# Zio_9DOF_IMU_LSM9DS1.net
KiCad netlist of a schematic drawn in EAGLE
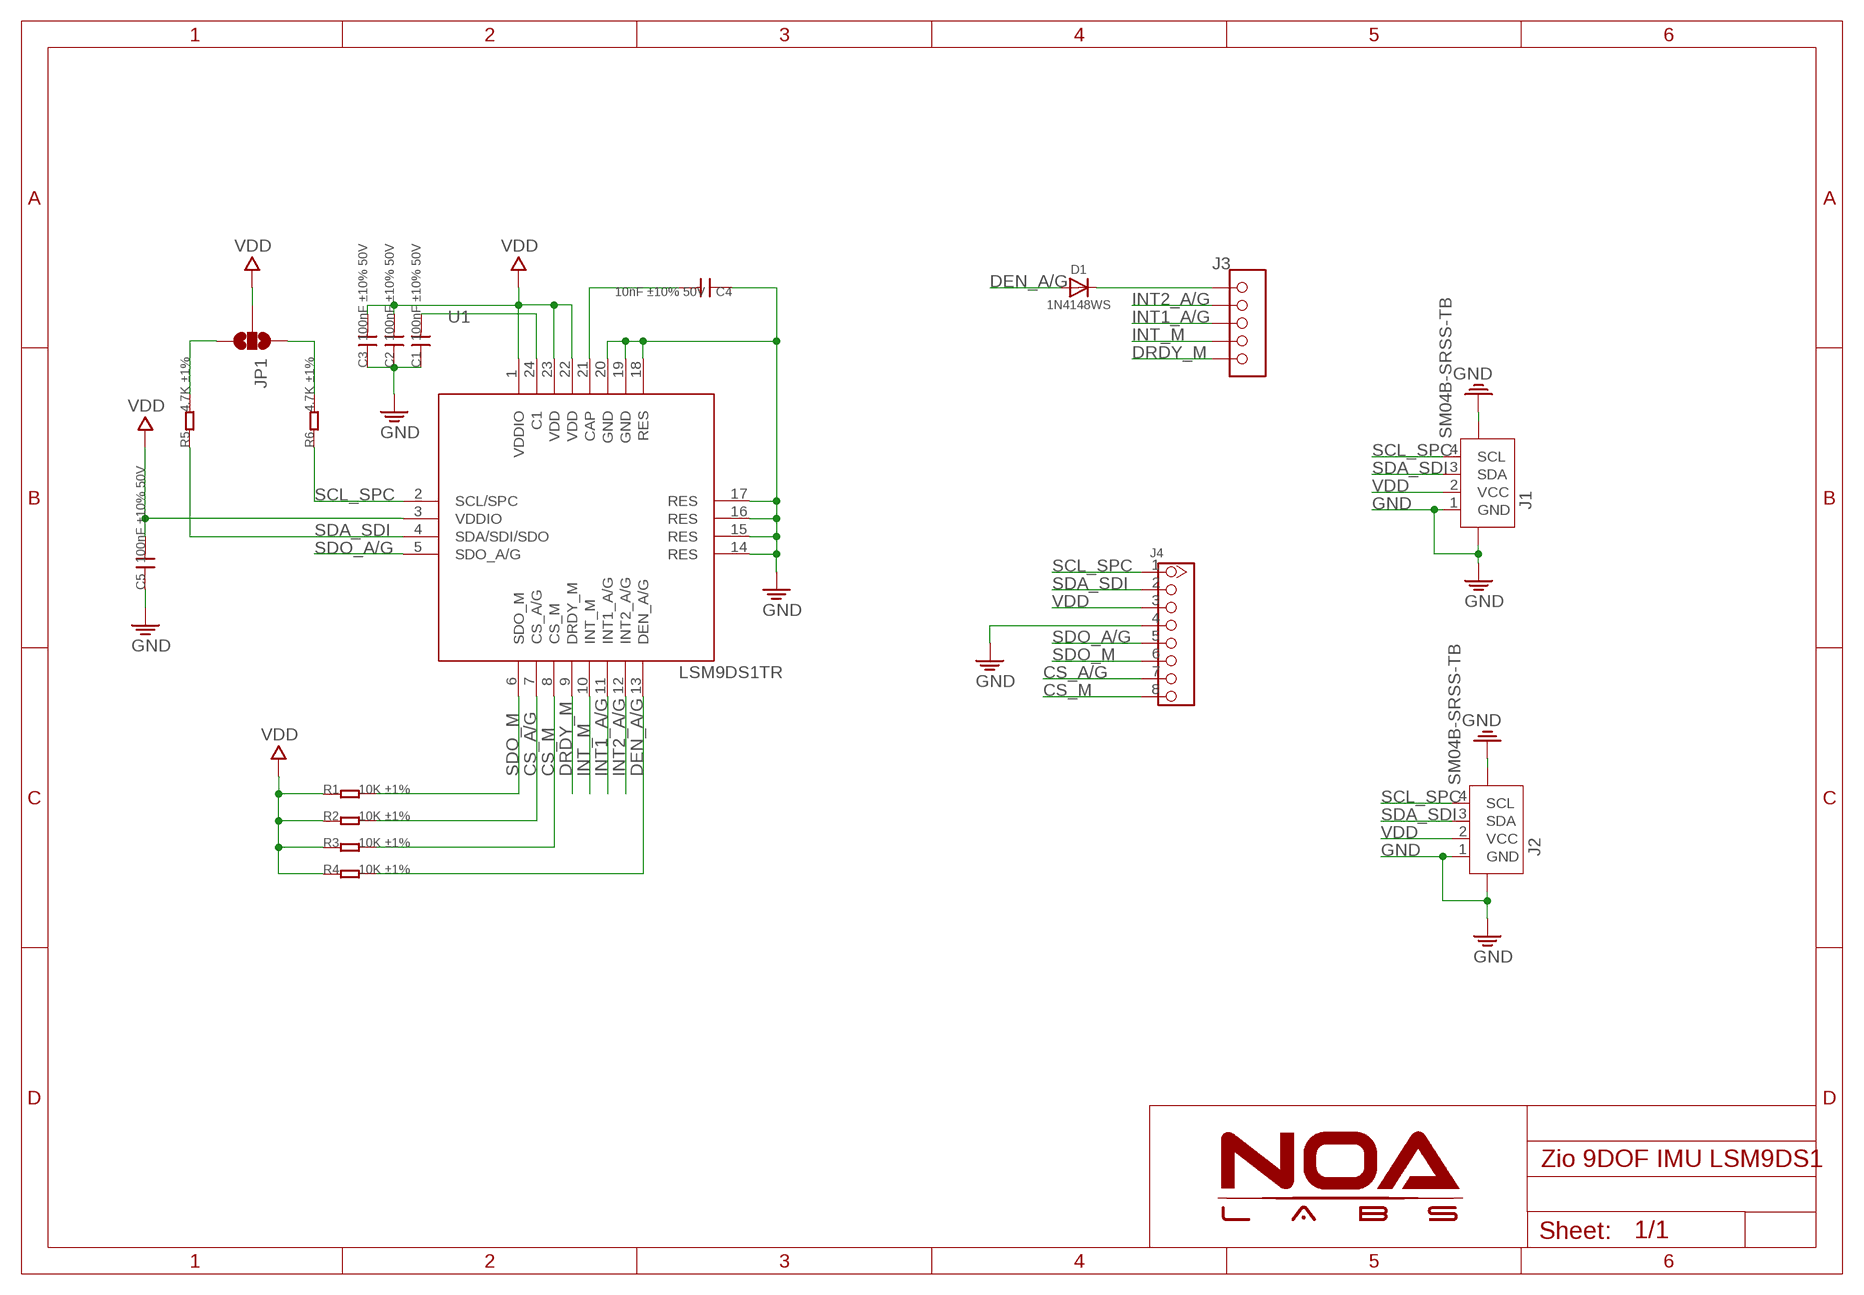
[diagram p0: schematic, sheet 1]

(export (version "E")
  (design (tool "Eeschema 10.0.6"))
  (components
    (comp (ref "C1")
      (value "100nF ±10% 50V")
      (footprint "eagle-import:0402")
      (libsource (lib "eagle-import") (part "C-0402"))
    )
    (comp (ref "C2")
      (value "100nF ±10% 50V")
      (footprint "eagle-import:0402")
      (libsource (lib "eagle-import") (part "C-0402"))
    )
    (comp (ref "C3")
      (value "100nF ±10% 50V")
      (footprint "eagle-import:0402")
      (libsource (lib "eagle-import") (part "C-0402"))
    )
    (comp (ref "C4")
      (value "10nF ±10% 50V")
      (footprint "eagle-import:0402")
      (libsource (lib "eagle-import") (part "C-0402"))
    )
    (comp (ref "C5")
      (value "100nF ±10% 50V")
      (footprint "eagle-import:0402")
      (libsource (lib "eagle-import") (part "C-0402"))
    )
    (comp (ref "D1")
      (value "1N4148WS")
      (footprint "eagle-import:SOD-323")
      (libsource (lib "eagle-import") (part "DIODESOD-323"))
    )
    (comp (ref "J1")
      (value "SM04B-SRSS-TB")
      (footprint "eagle-import:JST-SH-4P")
      (libsource (lib "eagle-import") (part "JST-SH-4P-1.0"))
    )
    (comp (ref "J2")
      (value "SM04B-SRSS-TB")
      (footprint "eagle-import:JST-SH-4P")
      (libsource (lib "eagle-import") (part "JST-SH-4P-1.0"))
    )
    (comp (ref "J3")
      (value "HEADER-5P-2.54")
      (footprint "eagle-import:5P-2.54")
      (libsource (lib "eagle-import") (part "HEADER-5P-2.54"))
    )
    (comp (ref "J4")
      (value "HEADER-8P-2.54")
      (footprint "eagle-import:8P-2.54")
      (libsource (lib "eagle-import") (part "HEADER-8P-2.54"))
    )
    (comp (ref "JP1")
      (value "JUMPER-SMT_3_2-NC_PASTE_NOCREM")
      (footprint "eagle-import:SMT-JUMPER_3_2-NC_PASTE_SILK_NOCREM")
      (libsource (lib "eagle-import") (part "JUMPER-SMT_3_2-NC_PASTE_NOCREM"))
    )
    (comp (ref "R1")
      (value "10K ±1%")
      (footprint "eagle-import:0402")
      (libsource (lib "eagle-import") (part "R-0402"))
    )
    (comp (ref "R2")
      (value "10K ±1%")
      (footprint "eagle-import:0402")
      (libsource (lib "eagle-import") (part "R-0402"))
    )
    (comp (ref "R3")
      (value "10K ±1%")
      (footprint "eagle-import:0402")
      (libsource (lib "eagle-import") (part "R-0402"))
    )
    (comp (ref "R4")
      (value "10K ±1%")
      (footprint "eagle-import:0402")
      (libsource (lib "eagle-import") (part "R-0402"))
    )
    (comp (ref "R5")
      (value "4.7K ±1%")
      (footprint "eagle-import:0402")
      (libsource (lib "eagle-import") (part "R-0402"))
    )
    (comp (ref "R6")
      (value "4.7K ±1%")
      (footprint "eagle-import:0402")
      (libsource (lib "eagle-import") (part "R-0402"))
    )
    (comp (ref "U1")
      (value "LSM9DS1TR")
      (footprint "eagle-import:LGA24")
      (libsource (lib "eagle-import") (part "LSM9DS1"))
    )
  )
  (nets
    (net (code "1") (name "/CS_A{slash}G") (class "Default")
      (node (ref "J4") (pin "7") (pinfunction "7_7") (pintype "bidirectional"))
      (node (ref "R2") (pin "2") (pinfunction "2_2") (pintype "passive"))
      (node (ref "U1") (pin "7") (pinfunction "CS_A/G_7") (pintype "bidirectional"))
    )
    (net (code "2") (name "/CS_M") (class "Default")
      (node (ref "J4") (pin "8") (pinfunction "8_8") (pintype "bidirectional"))
      (node (ref "R3") (pin "2") (pinfunction "2_2") (pintype "passive"))
      (node (ref "U1") (pin "8") (pinfunction "CS_M_8") (pintype "bidirectional"))
    )
    (net (code "3") (name "/DEN_A{slash}G") (class "Default")
      (node (ref "D1") (pin "A") (pinfunction "A_A") (pintype "passive"))
      (node (ref "R4") (pin "2") (pinfunction "2_2") (pintype "passive"))
      (node (ref "U1") (pin "13") (pinfunction "DEN_A/G_13") (pintype "bidirectional"))
    )
    (net (code "4") (name "/DRDY_M") (class "Default")
      (node (ref "J3") (pin "5") (pinfunction "5_5") (pintype "bidirectional"))
      (node (ref "U1") (pin "9") (pinfunction "DRDY_M_9") (pintype "bidirectional"))
    )
    (net (code "5") (name "/INT1_A{slash}G") (class "Default")
      (node (ref "J3") (pin "3") (pinfunction "3_3") (pintype "bidirectional"))
      (node (ref "U1") (pin "11") (pinfunction "INT1_A/G_11") (pintype "bidirectional"))
    )
    (net (code "6") (name "/INT2_A{slash}G") (class "Default")
      (node (ref "J3") (pin "2") (pinfunction "2_2") (pintype "bidirectional"))
      (node (ref "U1") (pin "12") (pinfunction "INT2_A/G_12") (pintype "bidirectional"))
    )
    (net (code "7") (name "/INT_M") (class "Default")
      (node (ref "J3") (pin "4") (pinfunction "4_4") (pintype "bidirectional"))
      (node (ref "U1") (pin "10") (pinfunction "INT_M_10") (pintype "bidirectional"))
    )
    (net (code "8") (name "/SCL_SPC") (class "Default")
      (node (ref "J1") (pin "4") (pinfunction "SCL_4") (pintype "bidirectional"))
      (node (ref "J2") (pin "4") (pinfunction "SCL_4") (pintype "bidirectional"))
      (node (ref "J4") (pin "1") (pinfunction "1_1") (pintype "bidirectional"))
      (node (ref "R6") (pin "1") (pinfunction "1_1") (pintype "passive"))
      (node (ref "U1") (pin "2") (pinfunction "SCL/SPC_2") (pintype "bidirectional"))
    )
    (net (code "9") (name "/SDA_SDI") (class "Default")
      (node (ref "J1") (pin "3") (pinfunction "SDA_3") (pintype "bidirectional"))
      (node (ref "J2") (pin "3") (pinfunction "SDA_3") (pintype "bidirectional"))
      (node (ref "J4") (pin "2") (pinfunction "2_2") (pintype "bidirectional"))
      (node (ref "R5") (pin "1") (pinfunction "1_1") (pintype "passive"))
      (node (ref "U1") (pin "4") (pinfunction "SDA/SDI/SDO_4") (pintype "bidirectional"))
    )
    (net (code "10") (name "/SDO_A{slash}G") (class "Default")
      (node (ref "J4") (pin "5") (pinfunction "5_5") (pintype "bidirectional"))
      (node (ref "U1") (pin "5") (pinfunction "SDO_A/G_5") (pintype "bidirectional"))
    )
    (net (code "11") (name "/SDO_M") (class "Default")
      (node (ref "J4") (pin "6") (pinfunction "6_6") (pintype "bidirectional"))
      (node (ref "R1") (pin "2") (pinfunction "2_2") (pintype "passive"))
      (node (ref "U1") (pin "6") (pinfunction "SDO_M_6") (pintype "bidirectional"))
    )
    (net (code "12") (name "GND") (class "Default")
      (node (ref "C1") (pin "1") (pinfunction "1_1") (pintype "passive"))
      (node (ref "C2") (pin "1") (pinfunction "1_1") (pintype "passive"))
      (node (ref "C3") (pin "1") (pinfunction "1_1") (pintype "passive"))
      (node (ref "C4") (pin "1") (pinfunction "1_1") (pintype "passive"))
      (node (ref "C5") (pin "1") (pinfunction "1_1") (pintype "passive"))
      (node (ref "J1") (pin "1") (pinfunction "GND_1") (pintype "bidirectional"))
      (node (ref "J1") (pin "NC1") (pinfunction "5_NC1") (pintype "bidirectional"))
      (node (ref "J1") (pin "NC2") (pinfunction "6_NC2") (pintype "bidirectional"))
      (node (ref "J2") (pin "1") (pinfunction "GND_1") (pintype "bidirectional"))
      (node (ref "J2") (pin "NC1") (pinfunction "5_NC1") (pintype "bidirectional"))
      (node (ref "J2") (pin "NC2") (pinfunction "6_NC2") (pintype "bidirectional"))
      (node (ref "J4") (pin "4") (pinfunction "4_4") (pintype "bidirectional"))
      (node (ref "U1") (pin "14") (pinfunction "RES_14") (pintype "bidirectional"))
      (node (ref "U1") (pin "15") (pinfunction "RES_15") (pintype "bidirectional"))
      (node (ref "U1") (pin "16") (pinfunction "RES_16") (pintype "bidirectional"))
      (node (ref "U1") (pin "17") (pinfunction "RES_17") (pintype "bidirectional"))
      (node (ref "U1") (pin "18") (pinfunction "RES_18") (pintype "bidirectional"))
      (node (ref "U1") (pin "19") (pinfunction "GND_19") (pintype "bidirectional"))
      (node (ref "U1") (pin "20") (pinfunction "GND_20") (pintype "bidirectional"))
    )
    (net (code "13") (name "Net-(D1-PadC)") (class "Default")
      (node (ref "D1") (pin "C") (pinfunction "C_C") (pintype "passive"))
      (node (ref "J3") (pin "1") (pinfunction "1_1") (pintype "bidirectional"))
    )
    (net (code "14") (name "Net-(JP1-Pad1)") (class "Default")
      (node (ref "JP1") (pin "1") (pinfunction "1_1") (pintype "passive"))
      (node (ref "R6") (pin "2") (pinfunction "2_2") (pintype "passive"))
    )
    (net (code "15") (name "Net-(JP1-Pad3)") (class "Default")
      (node (ref "JP1") (pin "3") (pinfunction "3_3") (pintype "passive"))
      (node (ref "R5") (pin "2") (pinfunction "2_2") (pintype "passive"))
    )
    (net (code "16") (name "Net-(U1-C1)") (class "Default")
      (node (ref "C1") (pin "2") (pinfunction "2_2") (pintype "passive"))
      (node (ref "U1") (pin "24") (pinfunction "C1_24") (pintype "bidirectional"))
    )
    (net (code "17") (name "Net-(U1-CAP)") (class "Default")
      (node (ref "C4") (pin "2") (pinfunction "2_2") (pintype "passive"))
      (node (ref "U1") (pin "21") (pinfunction "CAP_21") (pintype "bidirectional"))
    )
    (net (code "18") (name "VDD") (class "Default")
      (node (ref "C2") (pin "2") (pinfunction "2_2") (pintype "passive"))
      (node (ref "C3") (pin "2") (pinfunction "2_2") (pintype "passive"))
      (node (ref "C5") (pin "2") (pinfunction "2_2") (pintype "passive"))
      (node (ref "J1") (pin "2") (pinfunction "VCC_2") (pintype "bidirectional"))
      (node (ref "J2") (pin "2") (pinfunction "VCC_2") (pintype "bidirectional"))
      (node (ref "J4") (pin "3") (pinfunction "3_3") (pintype "bidirectional"))
      (node (ref "JP1") (pin "2") (pinfunction "2_2") (pintype "passive"))
      (node (ref "R1") (pin "1") (pinfunction "1_1") (pintype "passive"))
      (node (ref "R2") (pin "1") (pinfunction "1_1") (pintype "passive"))
      (node (ref "R3") (pin "1") (pinfunction "1_1") (pintype "passive"))
      (node (ref "R4") (pin "1") (pinfunction "1_1") (pintype "passive"))
      (node (ref "U1") (pin "1") (pinfunction "VDDIO_1") (pintype "bidirectional"))
      (node (ref "U1") (pin "22") (pinfunction "VDD_22") (pintype "bidirectional"))
      (node (ref "U1") (pin "23") (pinfunction "VDD_23") (pintype "bidirectional"))
      (node (ref "U1") (pin "3") (pinfunction "VDDIO_3") (pintype "bidirectional"))
    )
  )
)
